# v1.net
KiCad netlist of a schematic drawn in EAGLE
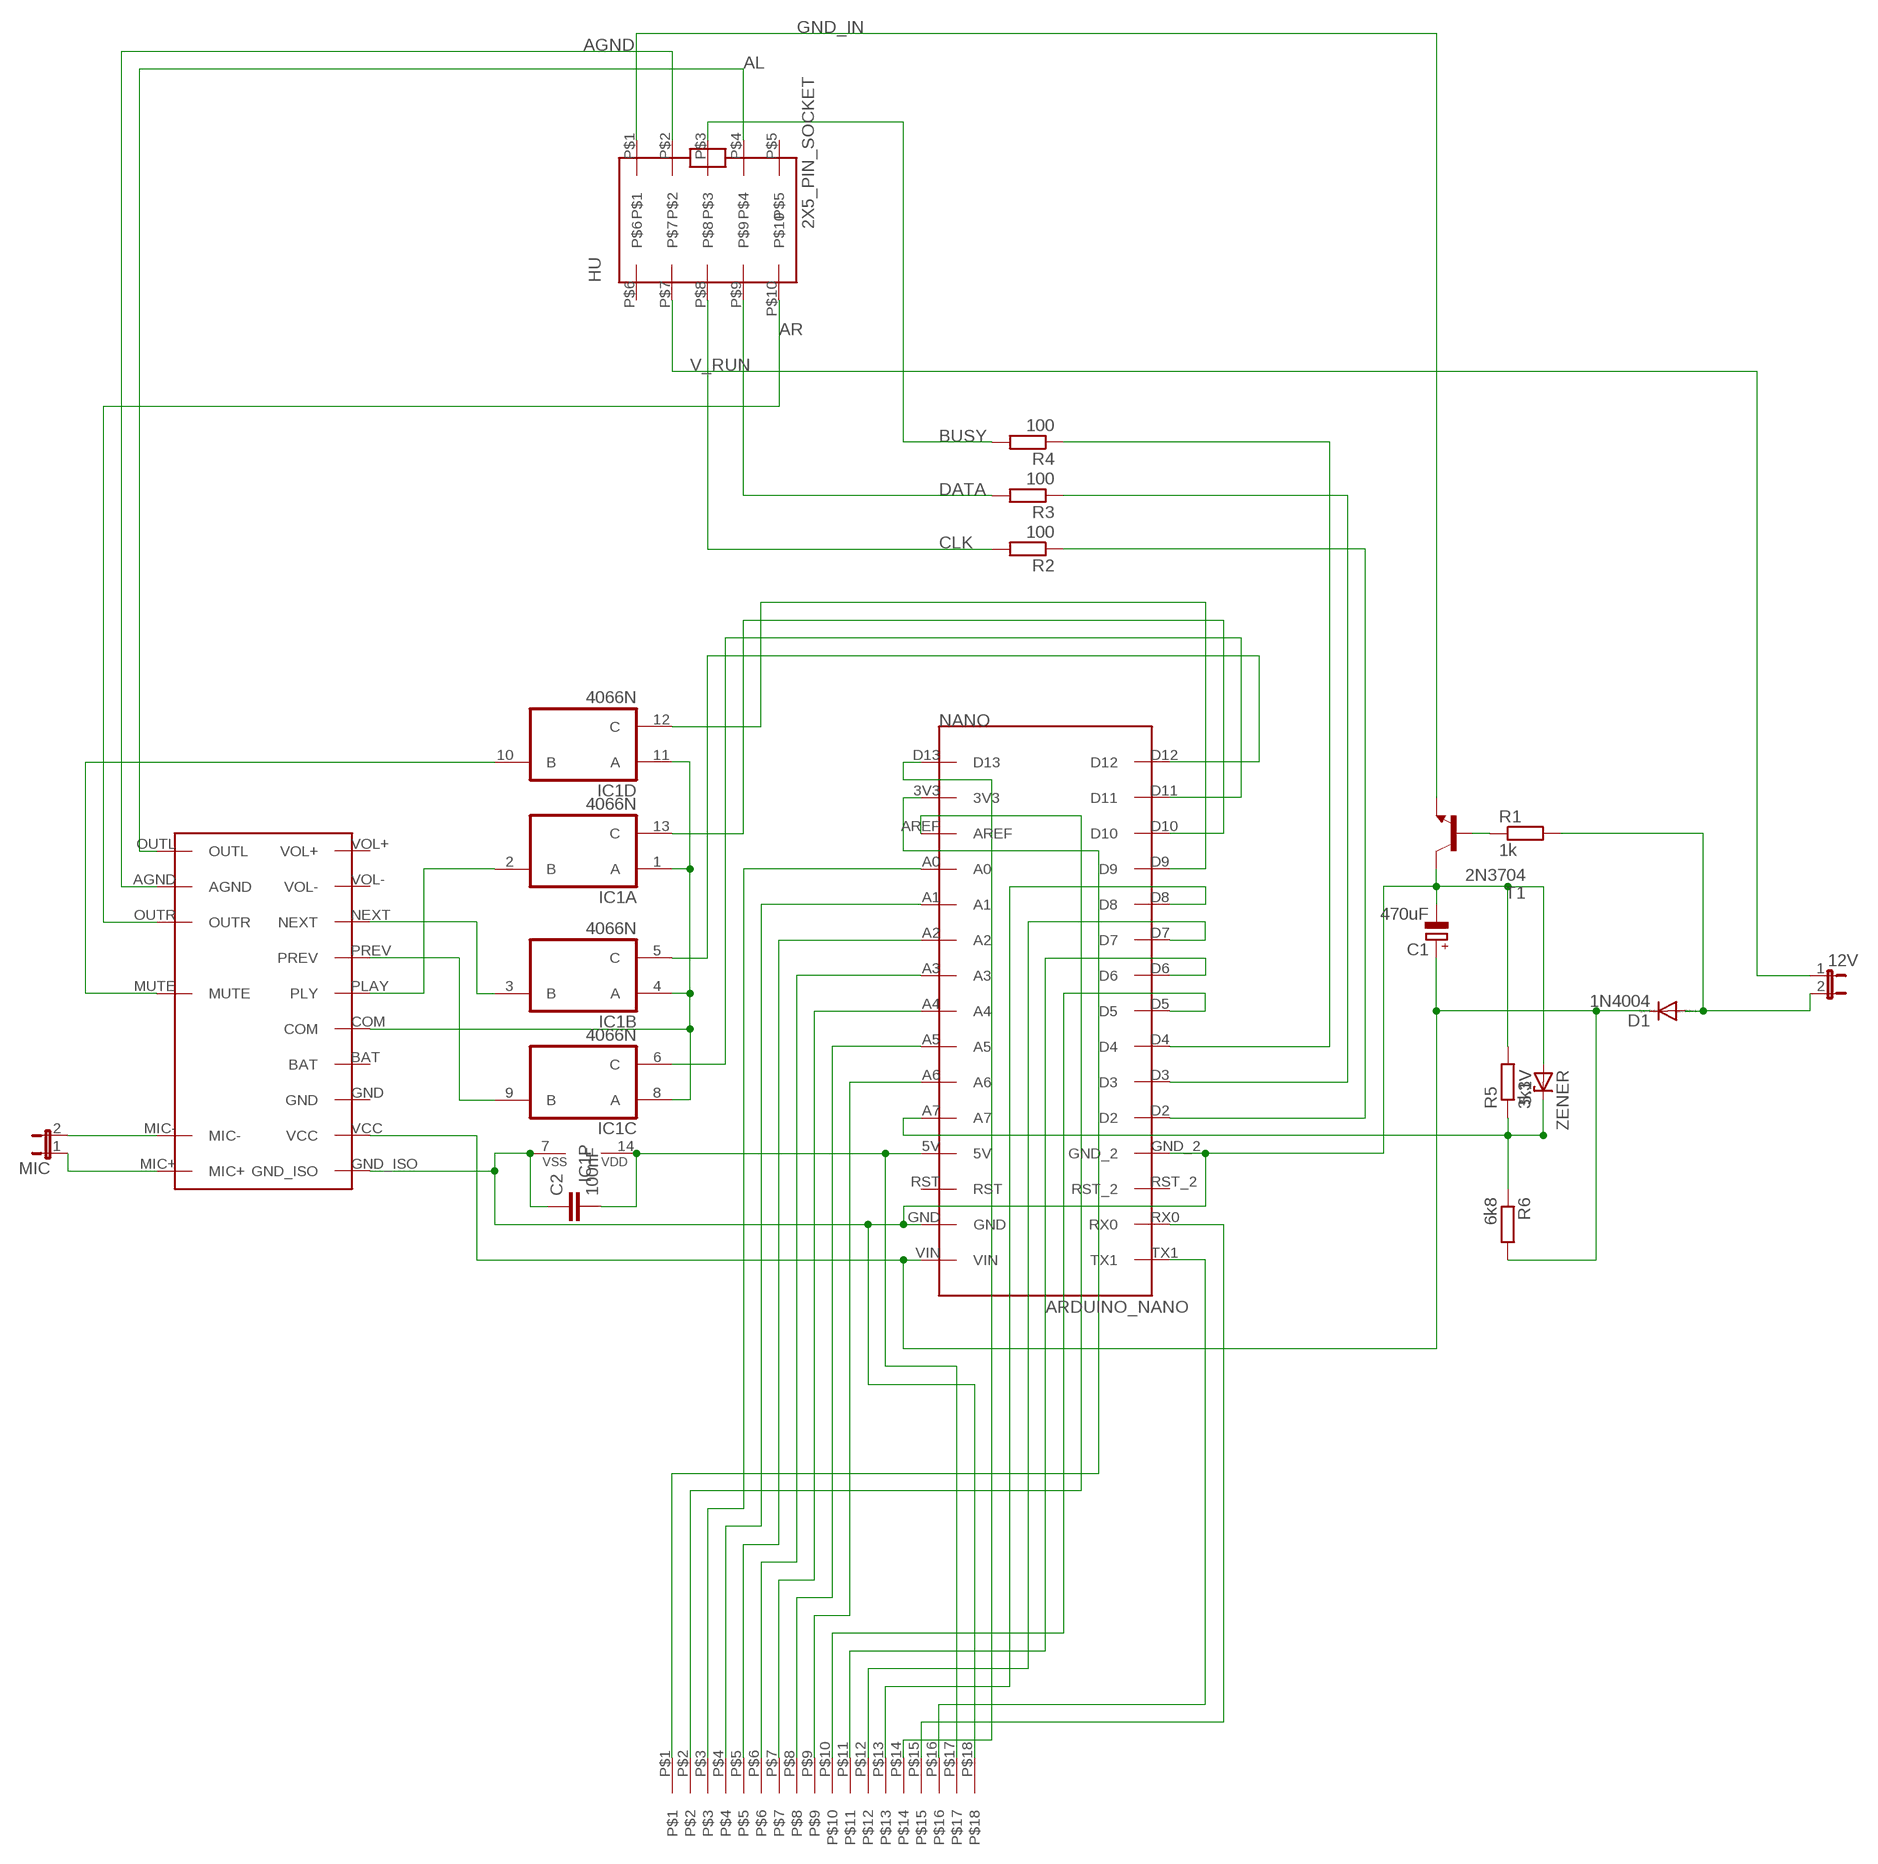
[diagram p0: schematic, sheet 1]

(export (version "E")
  (design (tool "Eeschema 10.0.6"))
  (components
    (comp (ref "12V")
      (value "JP1E")
      (footprint "eagle-import:JP1")
      (libsource (lib "eagle-import") (part "JP1E"))
    )
    (comp (ref "C1")
      (value "470uF")
      (footprint "eagle-import:E3,5-8")
      (libsource (lib "eagle-import") (part "CPOL-EUE3.5-8"))
    )
    (comp (ref "C2")
      (value "100nF")
      (footprint "eagle-import:C1206")
      (libsource (lib "eagle-import") (part "C-EUC1206"))
    )
    (comp (ref "D1")
      (value "1N4004")
      (footprint "eagle-import:DO41-10")
      (libsource (lib "eagle-import") (part "1N4004"))
    )
    (comp (ref "HU")
      (value "2X5_PIN_SOCKET")
      (footprint "eagle-import:2X5_PIN_SOCKET")
      (libsource (lib "eagle-import") (part "2X5_PIN_SOCKET"))
    )
    (comp (ref "IC1")
      (value "4066N")
      (footprint "eagle-import:DIL14")
      (libsource (lib "eagle-import") (part "4066N"))
    )
    (comp (ref "MIC")
      (value "JP1E")
      (footprint "eagle-import:JP1")
      (libsource (lib "eagle-import") (part "JP1E"))
    )
    (comp (ref "NANO")
      (value "ARDUINO_NANO")
      (footprint "eagle-import:ARDUINO_NANO")
      (libsource (lib "eagle-import") (part "ARDUINO_NANO"))
    )
    (comp (ref "R1")
      (value "1k")
      (footprint "eagle-import:0207_10")
      (libsource (lib "eagle-import") (part "R-EU_0207/10"))
    )
    (comp (ref "R2")
      (value "100")
      (footprint "eagle-import:0207_10")
      (libsource (lib "eagle-import") (part "R-EU_0207/10"))
    )
    (comp (ref "R3")
      (value "100")
      (footprint "eagle-import:0207_10")
      (libsource (lib "eagle-import") (part "R-EU_0207/10"))
    )
    (comp (ref "R4")
      (value "100")
      (footprint "eagle-import:0207_10")
      (libsource (lib "eagle-import") (part "R-EU_0207/10"))
    )
    (comp (ref "R5")
      (value "3k3")
      (footprint "eagle-import:0207_10")
      (libsource (lib "eagle-import") (part "R-EU_0207/10"))
    )
    (comp (ref "R6")
      (value "6k8")
      (footprint "eagle-import:0207_10")
      (libsource (lib "eagle-import") (part "R-EU_0207/10"))
    )
    (comp (ref "T1")
      (value "2N3704")
      (footprint "eagle-import:TO92")
      (libsource (lib "eagle-import") (part "2N3704"))
    )
    (comp (ref "U$1")
      (value "JMP18X1")
      (footprint "eagle-import:JMP18X1")
      (libsource (lib "eagle-import") (part "JMP18X1"))
    )
    (comp (ref "U$2")
      (value "CSR8645_MODULE")
      (footprint "eagle-import:CSR8645_MODULE")
      (libsource (lib "eagle-import") (part "CSR8645_MODULE"))
    )
    (comp (ref "ZENER")
      (value "5.1V")
      (footprint "eagle-import:DO41Z10")
      (libsource (lib "eagle-import") (part "ZENER-DIODEDO41Z10"))
    )
  )
  (nets
    (net (code "1") (name "/AGND") (class "Default")
      (node (ref "HU") (pin "P$2") (pinfunction "P$2_P$2") (pintype "bidirectional"))
      (node (ref "U$2") (pin "AGND") (pinfunction "AGND_AGND") (pintype "bidirectional"))
    )
    (net (code "2") (name "/AL") (class "Default")
      (node (ref "HU") (pin "P$4") (pinfunction "P$4_P$4") (pintype "bidirectional"))
      (node (ref "U$2") (pin "OUTL") (pinfunction "OUTL_OUTL") (pintype "bidirectional"))
    )
    (net (code "3") (name "/AR") (class "Default")
      (node (ref "HU") (pin "P$10") (pinfunction "P$10_P$10") (pintype "bidirectional"))
      (node (ref "U$2") (pin "OUTR") (pinfunction "OUTR_OUTR") (pintype "bidirectional"))
    )
    (net (code "4") (name "/BUSY") (class "Default")
      (node (ref "HU") (pin "P$3") (pinfunction "P$3_P$3") (pintype "bidirectional"))
      (node (ref "R4") (pin "2") (pinfunction "2_2") (pintype "passive"))
    )
    (net (code "5") (name "/CLK") (class "Default")
      (node (ref "HU") (pin "P$8") (pinfunction "P$8_P$8") (pintype "bidirectional"))
      (node (ref "R2") (pin "2") (pinfunction "2_2") (pintype "passive"))
    )
    (net (code "6") (name "/DATA") (class "Default")
      (node (ref "HU") (pin "P$9") (pinfunction "P$9_P$9") (pintype "bidirectional"))
      (node (ref "R3") (pin "2") (pinfunction "2_2") (pintype "passive"))
    )
    (net (code "7") (name "/GND_IN") (class "Default")
      (node (ref "HU") (pin "P$1") (pinfunction "P$1_P$1") (pintype "bidirectional"))
      (node (ref "T1") (pin "3") (pinfunction "E_3") (pintype "passive"))
    )
    (net (code "8") (name "/V_RUN") (class "Default")
      (node (ref "12V") (pin "1") (pinfunction "1_1") (pintype "passive"))
      (node (ref "HU") (pin "P$7") (pinfunction "P$7_P$7") (pintype "bidirectional"))
    )
    (net (code "9") (name "Net-(12V-Pad2)") (class "Default")
      (node (ref "12V") (pin "2") (pinfunction "2_2") (pintype "passive"))
      (node (ref "D1") (pin "A") (pinfunction "A_A") (pintype "passive"))
      (node (ref "R1") (pin "2") (pinfunction "2_2") (pintype "passive"))
    )
    (net (code "10") (name "Net-(C1-Pad+)") (class "Default")
      (node (ref "C1") (pin "+") (pinfunction "+_+") (pintype "passive"))
      (node (ref "D1") (pin "C") (pinfunction "C_C") (pintype "passive"))
      (node (ref "NANO") (pin "VIN") (pinfunction "VIN_VIN") (pintype "power_in"))
      (node (ref "R6") (pin "2") (pinfunction "2_2") (pintype "passive"))
      (node (ref "U$2") (pin "VCC") (pinfunction "VCC_VCC") (pintype "bidirectional"))
    )
    (net (code "11") (name "Net-(IC1A-A)") (class "Default")
      (node (ref "IC1") (pin "1") (pinfunction "A_1") (pintype "tri_state"))
      (node (ref "IC1") (pin "11") (pinfunction "A_11") (pintype "tri_state"))
      (node (ref "IC1") (pin "4") (pinfunction "A_4") (pintype "tri_state"))
      (node (ref "IC1") (pin "8") (pinfunction "A_8") (pintype "tri_state"))
      (node (ref "U$2") (pin "COM") (pinfunction "COM_COM") (pintype "bidirectional"))
    )
    (net (code "12") (name "Net-(IC1A-B)") (class "Default")
      (node (ref "IC1") (pin "2") (pinfunction "B_2") (pintype "tri_state"))
      (node (ref "U$2") (pin "PLAY") (pinfunction "PLY_PLAY") (pintype "bidirectional"))
    )
    (net (code "13") (name "Net-(IC1A-C)") (class "Default")
      (node (ref "IC1") (pin "13") (pinfunction "C_13") (pintype "input"))
      (node (ref "NANO") (pin "D10") (pinfunction "D10_D10") (pintype "bidirectional"))
    )
    (net (code "14") (name "Net-(IC1B-B)") (class "Default")
      (node (ref "IC1") (pin "3") (pinfunction "B_3") (pintype "tri_state"))
      (node (ref "U$2") (pin "NEXT") (pinfunction "NEXT_NEXT") (pintype "bidirectional"))
    )
    (net (code "15") (name "Net-(IC1B-C)") (class "Default")
      (node (ref "IC1") (pin "5") (pinfunction "C_5") (pintype "input"))
      (node (ref "NANO") (pin "D12") (pinfunction "D12_D12") (pintype "bidirectional"))
    )
    (net (code "16") (name "Net-(IC1C-B)") (class "Default")
      (node (ref "IC1") (pin "9") (pinfunction "B_9") (pintype "tri_state"))
      (node (ref "U$2") (pin "PREV") (pinfunction "PREV_PREV") (pintype "bidirectional"))
    )
    (net (code "17") (name "Net-(IC1C-C)") (class "Default")
      (node (ref "IC1") (pin "6") (pinfunction "C_6") (pintype "input"))
      (node (ref "NANO") (pin "D11") (pinfunction "D11_D11") (pintype "bidirectional"))
    )
    (net (code "18") (name "Net-(IC1D-B)") (class "Default")
      (node (ref "IC1") (pin "10") (pinfunction "B_10") (pintype "tri_state"))
      (node (ref "U$2") (pin "MUTE") (pinfunction "MUTE_MUTE") (pintype "bidirectional"))
    )
    (net (code "19") (name "Net-(IC1D-C)") (class "Default")
      (node (ref "IC1") (pin "12") (pinfunction "C_12") (pintype "input"))
      (node (ref "NANO") (pin "D9") (pinfunction "D9_D9") (pintype "bidirectional"))
    )
    (net (code "20") (name "Net-(IC1E-VDD)") (class "Default")
      (node (ref "C2") (pin "2") (pinfunction "2_2") (pintype "passive"))
      (node (ref "IC1") (pin "14") (pinfunction "VDD_14") (pintype "power_in"))
      (node (ref "NANO") (pin "5V") (pinfunction "5V_5V") (pintype "bidirectional"))
      (node (ref "U$1") (pin "P$17") (pinfunction "P$17_P$17") (pintype "bidirectional"))
    )
    (net (code "21") (name "Net-(IC1E-VSS)") (class "Default")
      (node (ref "C1") (pin "-") (pinfunction "-_-") (pintype "passive"))
      (node (ref "C2") (pin "1") (pinfunction "1_1") (pintype "passive"))
      (node (ref "IC1") (pin "7") (pinfunction "VSS_7") (pintype "power_in"))
      (node (ref "NANO") (pin "GND") (pinfunction "GND_GND") (pintype "power_in"))
      (node (ref "NANO") (pin "GND_2") (pinfunction "GND_2_GND_2") (pintype "power_in"))
      (node (ref "R5") (pin "2") (pinfunction "2_2") (pintype "passive"))
      (node (ref "T1") (pin "2") (pinfunction "C_2") (pintype "passive"))
      (node (ref "U$1") (pin "P$18") (pinfunction "P$18_P$18") (pintype "bidirectional"))
      (node (ref "U$2") (pin "GND_ISO") (pinfunction "GND_ISO_GND_ISO") (pintype "bidirectional"))
      (node (ref "ZENER") (pin "A") (pinfunction "A_A") (pintype "passive"))
    )
    (net (code "22") (name "Net-(MIC-Pad1)") (class "Default")
      (node (ref "MIC") (pin "1") (pinfunction "1_1") (pintype "passive"))
      (node (ref "U$2") (pin "MIC+") (pinfunction "MIC+_MIC+") (pintype "bidirectional"))
    )
    (net (code "23") (name "Net-(MIC-Pad2)") (class "Default")
      (node (ref "MIC") (pin "2") (pinfunction "2_2") (pintype "passive"))
      (node (ref "U$2") (pin "MIC-") (pinfunction "MIC-_MIC-") (pintype "bidirectional"))
    )
    (net (code "24") (name "Net-(NANO-Pad3V3)") (class "Default")
      (node (ref "NANO") (pin "3V3") (pinfunction "3V3_3V3") (pintype "bidirectional"))
      (node (ref "U$1") (pin "P$1") (pinfunction "P$1_P$1") (pintype "bidirectional"))
    )
    (net (code "25") (name "Net-(NANO-PadA0)") (class "Default")
      (node (ref "NANO") (pin "A0") (pinfunction "A0_A0") (pintype "bidirectional"))
      (node (ref "U$1") (pin "P$3") (pinfunction "P$3_P$3") (pintype "bidirectional"))
    )
    (net (code "26") (name "Net-(NANO-PadA1)") (class "Default")
      (node (ref "NANO") (pin "A1") (pinfunction "A1_A1") (pintype "bidirectional"))
      (node (ref "U$1") (pin "P$4") (pinfunction "P$4_P$4") (pintype "bidirectional"))
    )
    (net (code "27") (name "Net-(NANO-PadA2)") (class "Default")
      (node (ref "NANO") (pin "A2") (pinfunction "A2_A2") (pintype "bidirectional"))
      (node (ref "U$1") (pin "P$5") (pinfunction "P$5_P$5") (pintype "bidirectional"))
    )
    (net (code "28") (name "Net-(NANO-PadA3)") (class "Default")
      (node (ref "NANO") (pin "A3") (pinfunction "A3_A3") (pintype "bidirectional"))
      (node (ref "U$1") (pin "P$6") (pinfunction "P$6_P$6") (pintype "bidirectional"))
    )
    (net (code "29") (name "Net-(NANO-PadA4)") (class "Default")
      (node (ref "NANO") (pin "A4") (pinfunction "A4_A4") (pintype "bidirectional"))
      (node (ref "U$1") (pin "P$7") (pinfunction "P$7_P$7") (pintype "bidirectional"))
    )
    (net (code "30") (name "Net-(NANO-PadA5)") (class "Default")
      (node (ref "NANO") (pin "A5") (pinfunction "A5_A5") (pintype "bidirectional"))
      (node (ref "U$1") (pin "P$8") (pinfunction "P$8_P$8") (pintype "bidirectional"))
    )
    (net (code "31") (name "Net-(NANO-PadA6)") (class "Default")
      (node (ref "NANO") (pin "A6") (pinfunction "A6_A6") (pintype "bidirectional"))
      (node (ref "U$1") (pin "P$9") (pinfunction "P$9_P$9") (pintype "bidirectional"))
    )
    (net (code "32") (name "Net-(NANO-PadA7)") (class "Default")
      (node (ref "NANO") (pin "A7") (pinfunction "A7_A7") (pintype "bidirectional"))
      (node (ref "R5") (pin "1") (pinfunction "1_1") (pintype "passive"))
      (node (ref "R6") (pin "1") (pinfunction "1_1") (pintype "passive"))
      (node (ref "ZENER") (pin "C") (pinfunction "C_C") (pintype "passive"))
    )
    (net (code "33") (name "Net-(NANO-PadAREF)") (class "Default")
      (node (ref "NANO") (pin "AREF") (pinfunction "AREF_AREF") (pintype "bidirectional"))
      (node (ref "U$1") (pin "P$2") (pinfunction "P$2_P$2") (pintype "bidirectional"))
    )
    (net (code "34") (name "Net-(NANO-PadD2)") (class "Default")
      (node (ref "NANO") (pin "D2") (pinfunction "D2_D2") (pintype "bidirectional"))
      (node (ref "R2") (pin "1") (pinfunction "1_1") (pintype "passive"))
    )
    (net (code "35") (name "Net-(NANO-PadD3)") (class "Default")
      (node (ref "NANO") (pin "D3") (pinfunction "D3_D3") (pintype "bidirectional"))
      (node (ref "R3") (pin "1") (pinfunction "1_1") (pintype "passive"))
    )
    (net (code "36") (name "Net-(NANO-PadD4)") (class "Default")
      (node (ref "NANO") (pin "D4") (pinfunction "D4_D4") (pintype "bidirectional"))
      (node (ref "R4") (pin "1") (pinfunction "1_1") (pintype "passive"))
    )
    (net (code "37") (name "Net-(NANO-PadD5)") (class "Default")
      (node (ref "NANO") (pin "D5") (pinfunction "D5_D5") (pintype "bidirectional"))
      (node (ref "U$1") (pin "P$10") (pinfunction "P$10_P$10") (pintype "bidirectional"))
    )
    (net (code "38") (name "Net-(NANO-PadD6)") (class "Default")
      (node (ref "NANO") (pin "D6") (pinfunction "D6_D6") (pintype "bidirectional"))
      (node (ref "U$1") (pin "P$11") (pinfunction "P$11_P$11") (pintype "bidirectional"))
    )
    (net (code "39") (name "Net-(NANO-PadD7)") (class "Default")
      (node (ref "NANO") (pin "D7") (pinfunction "D7_D7") (pintype "bidirectional"))
      (node (ref "U$1") (pin "P$12") (pinfunction "P$12_P$12") (pintype "bidirectional"))
    )
    (net (code "40") (name "Net-(NANO-PadD8)") (class "Default")
      (node (ref "NANO") (pin "D8") (pinfunction "D8_D8") (pintype "bidirectional"))
      (node (ref "U$1") (pin "P$13") (pinfunction "P$13_P$13") (pintype "bidirectional"))
    )
    (net (code "41") (name "Net-(NANO-PadD13)") (class "Default")
      (node (ref "NANO") (pin "D13") (pinfunction "D13_D13") (pintype "bidirectional"))
      (node (ref "U$1") (pin "P$14") (pinfunction "P$14_P$14") (pintype "bidirectional"))
    )
    (net (code "42") (name "Net-(NANO-PadRX0)") (class "Default")
      (node (ref "NANO") (pin "RX0") (pinfunction "RX0_RX0") (pintype "bidirectional"))
      (node (ref "U$1") (pin "P$15") (pinfunction "P$15_P$15") (pintype "bidirectional"))
    )
    (net (code "43") (name "Net-(NANO-PadTX1)") (class "Default")
      (node (ref "NANO") (pin "TX1") (pinfunction "TX1_TX1") (pintype "bidirectional"))
      (node (ref "U$1") (pin "P$16") (pinfunction "P$16_P$16") (pintype "bidirectional"))
    )
    (net (code "44") (name "Net-(T1-B)") (class "Default")
      (node (ref "R1") (pin "1") (pinfunction "1_1") (pintype "passive"))
      (node (ref "T1") (pin "1") (pinfunction "B_1") (pintype "passive"))
    )
    (net (code "45") (name "unconnected-(HU-PadP$5)") (class "Default")
      (node (ref "HU") (pin "P$5") (pinfunction "P$5_P$5") (pintype "bidirectional"))
    )
    (net (code "46") (name "unconnected-(HU-PadP$6)") (class "Default")
      (node (ref "HU") (pin "P$6") (pinfunction "P$6_P$6") (pintype "bidirectional"))
    )
    (net (code "47") (name "unconnected-(NANO-PadRST)") (class "Default")
      (node (ref "NANO") (pin "RST") (pinfunction "RST_RST") (pintype "bidirectional"))
    )
    (net (code "48") (name "unconnected-(NANO-PadRST_2)") (class "Default")
      (node (ref "NANO") (pin "RST_2") (pinfunction "RST_2_RST_2") (pintype "bidirectional"))
    )
    (net (code "49") (name "unconnected-(U$2-PadBAT)") (class "Default")
      (node (ref "U$2") (pin "BAT") (pinfunction "BAT_BAT") (pintype "bidirectional"))
    )
    (net (code "50") (name "unconnected-(U$2-PadGND)") (class "Default")
      (node (ref "U$2") (pin "GND") (pinfunction "GND_GND") (pintype "bidirectional"))
    )
    (net (code "51") (name "unconnected-(U$2-PadVOL+)") (class "Default")
      (node (ref "U$2") (pin "VOL+") (pinfunction "VOL+_VOL+") (pintype "bidirectional"))
    )
    (net (code "52") (name "unconnected-(U$2-PadVOL-)") (class "Default")
      (node (ref "U$2") (pin "VOL-") (pinfunction "VOL-_VOL-") (pintype "bidirectional"))
    )
  )
)
